# IMX7S_WIRELESS.net
KiCad netlist of a schematic drawn in Altium Designer
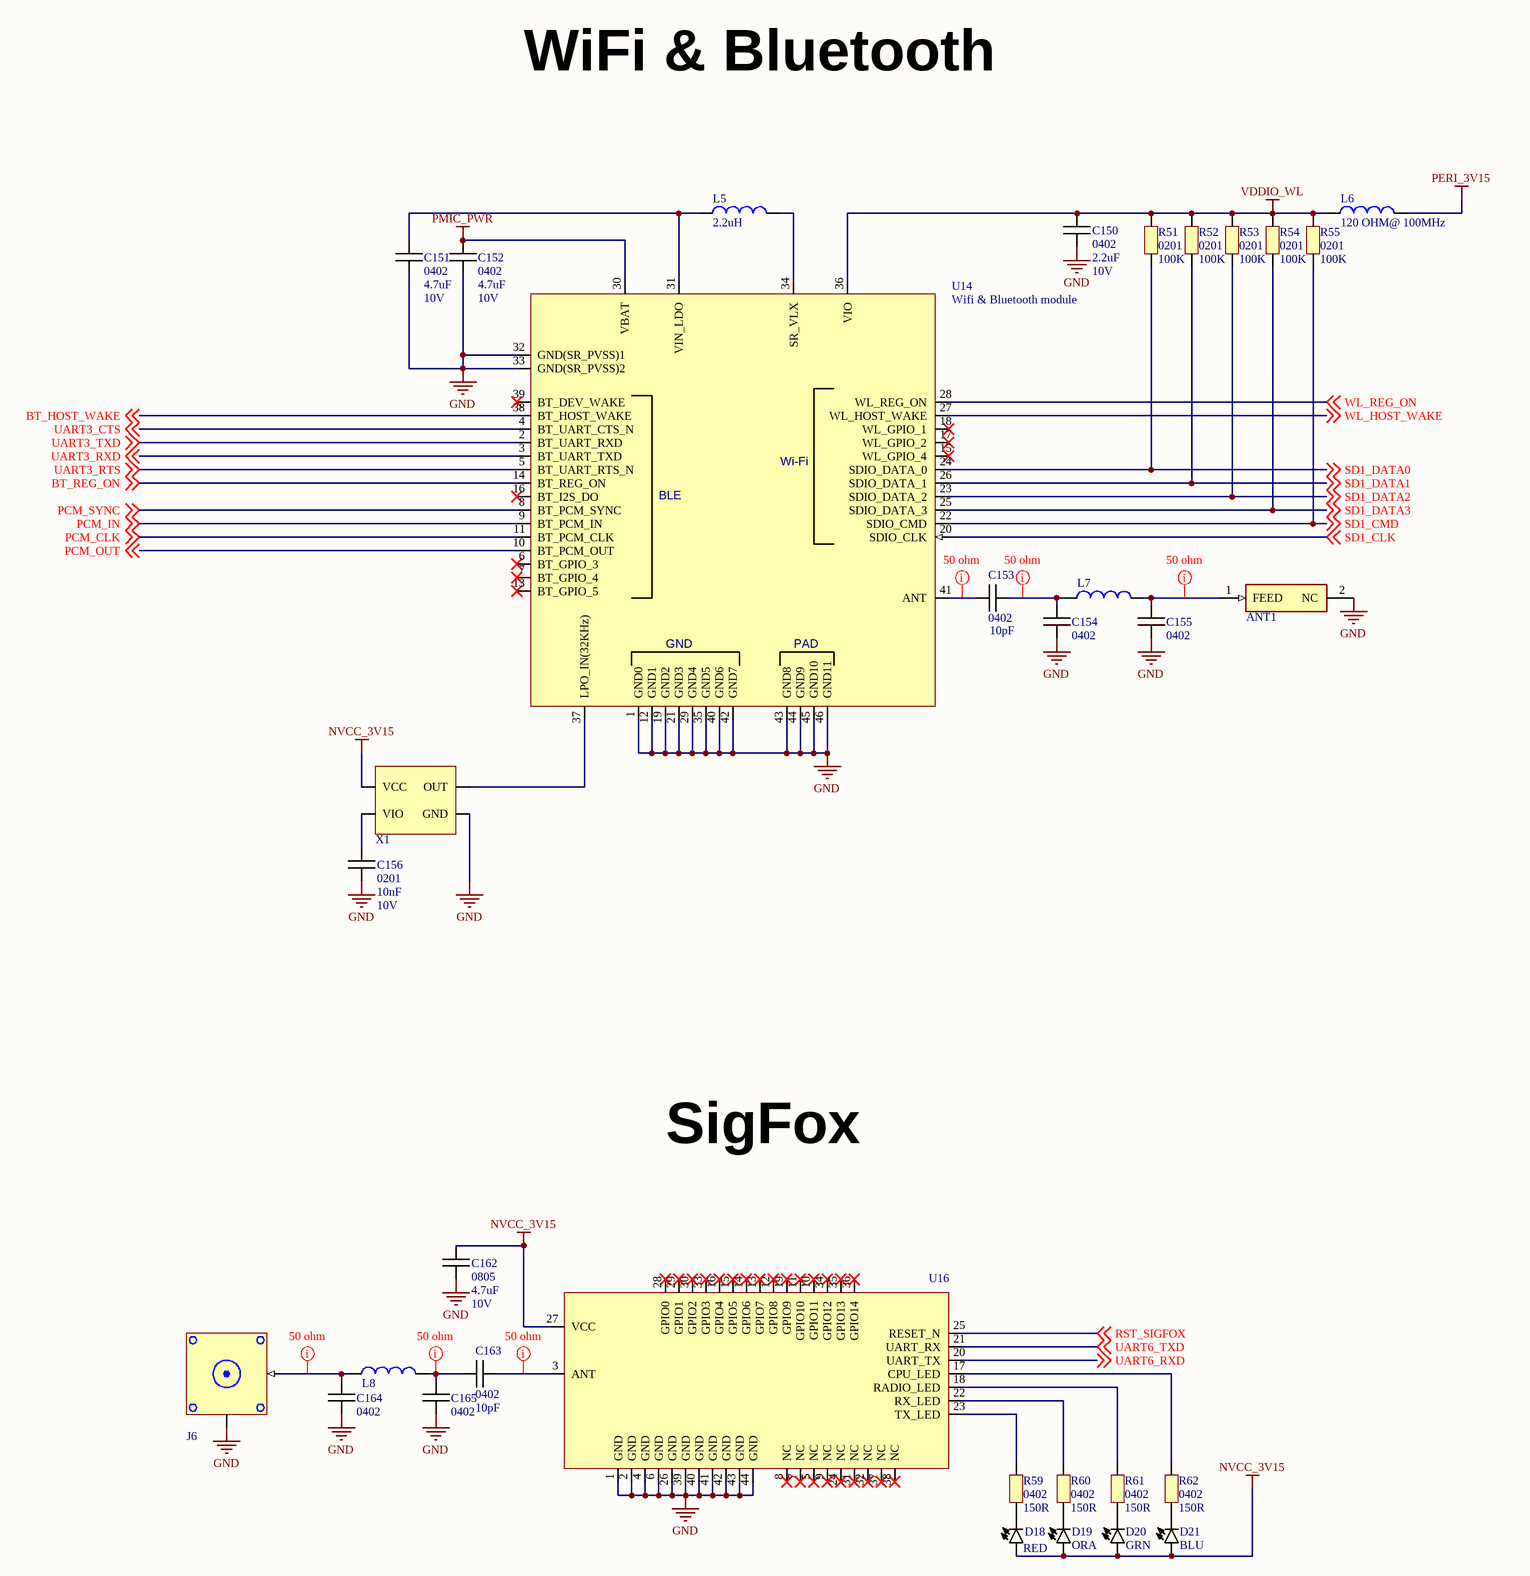
[diagram p0: IMX7S_WIRELESS.SchDoc]

(export (version "E")
  (design (tool "Eeschema 10.0.6"))
  (components
    (comp (ref "ANT1")
      (value "SRCW004")
      (footprint "SRCW004")
      (description "Antenna")
      (fields (field (name "MOUSER PART NUMBER") "237-SRCW004"))
      (libsource (lib "Schlib_IMX7") (part "SRCW004"))
    )
    (comp (ref "C150")
      (value "2.2uF")
      (footprint "C0402")
      (fields
        (field (name "PACKAGE") "0402")
        (field (name "VOLTAGE") "10V")
        (field (name "TOLERANCE") "20%")
        (field (name "Comment") "C0402")
      )
      (libsource (lib "Schlib_IMX7") (part "C0402"))
    )
    (comp (ref "C151")
      (value "4.7uF")
      (footprint "C0402")
      (fields (field (name "PACKAGE") "0402") (field (name "VOLTAGE") "10V") (field (name "Comment") "C0402"))
      (libsource (lib "Schlib_IMX7") (part "C0402"))
    )
    (comp (ref "C152")
      (value "4.7uF")
      (footprint "C0402")
      (fields (field (name "PACKAGE") "0402") (field (name "VOLTAGE") "10V") (field (name "Comment") "C0402"))
      (libsource (lib "Schlib_IMX7") (part "C0402"))
    )
    (comp (ref "C153")
      (value "10pF")
      (footprint "C0402")
      (fields
        (field (name "PACKAGE") "0402")
        (field (name "VOLTAGE") "0V")
        (field (name "TOLERANCE") "1%")
        (field (name "Comment") "C0402")
      )
      (libsource (lib "Schlib_IMX7") (part "C0402"))
    )
    (comp (ref "C154")
      (value "C0402")
      (footprint "C0402")
      (fields (field (name "PACKAGE") "0402") (field (name "VOLTAGE") "0V"))
      (libsource (lib "Schlib_IMX7") (part "C0402"))
    )
    (comp (ref "C155")
      (value "C0402")
      (footprint "C0402")
      (fields (field (name "PACKAGE") "0402") (field (name "VOLTAGE") "0V"))
      (libsource (lib "Schlib_IMX7") (part "C0402"))
    )
    (comp (ref "C156")
      (value "10nF")
      (footprint "C0201")
      (fields (field (name "PACKAGE") "0201") (field (name "VOLTAGE") "10V") (field (name "Comment") "C0201"))
      (libsource (lib "Schlib_IMX7") (part "C0201"))
    )
    (comp (ref "C162")
      (value "4.7uF")
      (footprint "C0805")
      (description "Cap Ceramic 4.7uF 10V X5R 10% SMD 0805 85C Plastic T/R")
      (fields
        (field (name "PACKAGE") "0805")
        (field (name "VOLTAGE") "10V")
        (field (name "TOLERANCE") "10%")
        (field (name "Comment") "C0805")
      )
      (libsource (lib "Schlib_IMX7") (part "C0805"))
    )
    (comp (ref "C163")
      (value "10pF")
      (footprint "C0402")
      (fields
        (field (name "PACKAGE") "0402")
        (field (name "VOLTAGE") "0V")
        (field (name "TOLERANCE") "1%")
        (field (name "Comment") "C0402")
      )
      (libsource (lib "Schlib_IMX7") (part "C0402"))
    )
    (comp (ref "C164")
      (value "C0402")
      (footprint "C0402")
      (fields (field (name "PACKAGE") "0402") (field (name "VOLTAGE") "0V"))
      (libsource (lib "Schlib_IMX7") (part "C0402"))
    )
    (comp (ref "C165")
      (value "C0402")
      (footprint "C0402")
      (fields (field (name "PACKAGE") "0402") (field (name "VOLTAGE") "0V"))
      (libsource (lib "Schlib_IMX7") (part "C0402"))
    )
    (comp (ref "D18") (value "RED") (footprint "D0603") (libsource (lib "Schlib_IMX7") (part "LED")))
    (comp (ref "D19") (value "ORA") (footprint "D0603") (libsource (lib "Schlib_IMX7") (part "LED")))
    (comp (ref "D20") (value "GRN") (footprint "D0603") (libsource (lib "Schlib_IMX7") (part "LED")))
    (comp (ref "D21") (value "BLU") (footprint "D0603") (libsource (lib "Schlib_IMX7") (part "LED")))
    (comp (ref "J6") (value "SMA") (footprint "SMA") (libsource (lib "Schlib_IMX7") (part "SMA")))
    (comp (ref "L5")
      (value "2.2uH")
      (footprint "R0402")
      (fields (field (name "Comment") "Self"))
      (libsource (lib "Schlib_IMX7") (part "Self"))
    )
    (comp (ref "L6")
      (value "120 OHM@ 100MHz")
      (footprint "SELF")
      (fields (field (name "Comment") "Self"))
      (libsource (lib "Schlib_IMX7") (part "Self"))
    )
    (comp (ref "L7") (value "Self") (footprint "R0402") (libsource (lib "Schlib_IMX7") (part "Self")))
    (comp (ref "L8") (value "Self") (footprint "R0402") (libsource (lib "Schlib_IMX7") (part "Self")))
    (comp (ref "R51")
      (value "100K")
      (footprint "R0201")
      (description "MULTICOMP - MCRE000188 - RES, 100K, 1%, 0.05W, 0201, THICK FILM")
      (fields (field (name "PACKAGE") "0201") (field (name "VOLTAGE") "0V") (field (name "TOLERANCE") "1%"))
      (libsource (lib "Schlib_IMX7") (part "R0201"))
    )
    (comp (ref "R52")
      (value "100K")
      (footprint "R0201")
      (description "MULTICOMP - MCRE000188 - RES, 100K, 1%, 0.05W, 0201, THICK FILM")
      (fields (field (name "PACKAGE") "0201") (field (name "VOLTAGE") "0V") (field (name "TOLERANCE") "1%"))
      (libsource (lib "Schlib_IMX7") (part "R0201"))
    )
    (comp (ref "R53")
      (value "100K")
      (footprint "R0201")
      (description "MULTICOMP - MCRE000188 - RES, 100K, 1%, 0.05W, 0201, THICK FILM")
      (fields (field (name "PACKAGE") "0201") (field (name "VOLTAGE") "0V") (field (name "TOLERANCE") "1%"))
      (libsource (lib "Schlib_IMX7") (part "R0201"))
    )
    (comp (ref "R54")
      (value "100K")
      (footprint "R0201")
      (description "MULTICOMP - MCRE000188 - RES, 100K, 1%, 0.05W, 0201, THICK FILM")
      (fields (field (name "PACKAGE") "0201") (field (name "VOLTAGE") "0V") (field (name "TOLERANCE") "1%"))
      (libsource (lib "Schlib_IMX7") (part "R0201"))
    )
    (comp (ref "R55")
      (value "100K")
      (footprint "R0201")
      (description "MULTICOMP - MCRE000188 - RES, 100K, 1%, 0.05W, 0201, THICK FILM")
      (fields (field (name "PACKAGE") "0201") (field (name "VOLTAGE") "0V") (field (name "TOLERANCE") "1%"))
      (libsource (lib "Schlib_IMX7") (part "R0201"))
    )
    (comp (ref "R59")
      (value "150R")
      (footprint "R0402")
      (description "TE Connectivity CRG0402 Series Thick Film Surface Mount Resistor 0402 Case 150 1% 0.063W 100ppm/C")
      (fields (field (name "PACKAGE") "0402") (field (name "VOLTAGE") "0V") (field (name "TOLERANCE") "1%"))
      (libsource (lib "Schlib_IMX7") (part "R0402"))
    )
    (comp (ref "R60")
      (value "150R")
      (footprint "R0402")
      (description "TE Connectivity CRG0402 Series Thick Film Surface Mount Resistor 0402 Case 150 1% 0.063W 100ppm/C")
      (fields (field (name "PACKAGE") "0402") (field (name "VOLTAGE") "0V") (field (name "TOLERANCE") "1%"))
      (libsource (lib "Schlib_IMX7") (part "R0402"))
    )
    (comp (ref "R61")
      (value "150R")
      (footprint "R0402")
      (description "TE Connectivity CRG0402 Series Thick Film Surface Mount Resistor 0402 Case 150 1% 0.063W 100ppm/C")
      (fields (field (name "PACKAGE") "0402") (field (name "VOLTAGE") "0V") (field (name "TOLERANCE") "1%"))
      (libsource (lib "Schlib_IMX7") (part "R0402"))
    )
    (comp (ref "R62")
      (value "150R")
      (footprint "R0402")
      (description "TE Connectivity CRG0402 Series Thick Film Surface Mount Resistor 0402 Case 150 1% 0.063W 100ppm/C")
      (fields (field (name "PACKAGE") "0402") (field (name "VOLTAGE") "0V") (field (name "TOLERANCE") "1%"))
      (libsource (lib "Schlib_IMX7") (part "R0402"))
    )
    (comp (ref "U14")
      (value "Wifi & Bluetooth module")
      (footprint "LBEE5KL1DX")
      (libsource (lib "Schlib_IMX7") (part "LBEE5KL1X-833"))
    )
    (comp (ref "U16")
      (value "AX-SIP-SFEU-1-01-TX30")
      (footprint "AX-SIP-SFEU-1-01-TX30")
      (libsource (lib "Schlib_IMX7") (part "AX-SIP-SFEU-1-01-TX30"))
    )
    (comp (ref "X1")
      (value "X1B0002110001 SG-3030CM 32.768KHZ B")
      (footprint "SPXO")
      (libsource (lib "Schlib_IMX7") (part "Oscillateur"))
    )
  )
  (nets
    (net (code "1") (name "BT_HOST_WAKE") (class "Default")
      (node (ref "U14") (pin "38") (pinfunction "BT_HOST_WAKE_38") (pintype "passive"))
    )
    (net (code "2") (name "BT_REG_ON") (class "Default")
      (node (ref "U14") (pin "14") (pinfunction "BT_REG_ON_14") (pintype "passive"))
    )
    (net (code "3") (name "GND") (class "Default")
      (node (ref "ANT1") (pin "2") (pinfunction "NC_2") (pintype "passive"))
      (node (ref "C150") (pin "1") (pinfunction "1_1") (pintype "passive"))
      (node (ref "C151") (pin "1") (pinfunction "1_1") (pintype "passive"))
      (node (ref "C152") (pin "1") (pinfunction "1_1") (pintype "passive"))
      (node (ref "C154") (pin "1") (pinfunction "1_1") (pintype "passive"))
      (node (ref "C155") (pin "1") (pinfunction "1_1") (pintype "passive"))
      (node (ref "C156") (pin "1") (pinfunction "1_1") (pintype "passive"))
      (node (ref "C162") (pin "1") (pinfunction "1_1") (pintype "passive"))
      (node (ref "C164") (pin "1") (pinfunction "1_1") (pintype "passive"))
      (node (ref "C165") (pin "1") (pinfunction "1_1") (pintype "passive"))
      (node (ref "J6") (pin "2") (pinfunction "GND_2") (pintype "passive"))
      (node (ref "U14") (pin "1") (pinfunction "GND0_1") (pintype "passive"))
      (node (ref "U14") (pin "12") (pinfunction "GND1_12") (pintype "passive"))
      (node (ref "U14") (pin "19") (pinfunction "GND2_19") (pintype "passive"))
      (node (ref "U14") (pin "21") (pinfunction "GND3_21") (pintype "passive"))
      (node (ref "U14") (pin "29") (pinfunction "GND4_29") (pintype "passive"))
      (node (ref "U14") (pin "32") (pinfunction "GND(SR_PVSS)1_32") (pintype "passive"))
      (node (ref "U14") (pin "33") (pinfunction "GND(SR_PVSS)2_33") (pintype "passive"))
      (node (ref "U14") (pin "35") (pinfunction "GND5_35") (pintype "passive"))
      (node (ref "U14") (pin "40") (pinfunction "GND6_40") (pintype "passive"))
      (node (ref "U14") (pin "42") (pinfunction "GND7_42") (pintype "passive"))
      (node (ref "U14") (pin "43") (pinfunction "GND8_43") (pintype "passive"))
      (node (ref "U14") (pin "44") (pinfunction "GND9_44") (pintype "passive"))
      (node (ref "U14") (pin "45") (pinfunction "GND10_45") (pintype "passive"))
      (node (ref "U14") (pin "46") (pinfunction "GND11_46") (pintype "passive"))
      (node (ref "U16") (pin "1") (pinfunction "GND_1") (pintype "passive"))
      (node (ref "U16") (pin "2") (pinfunction "GND_2") (pintype "passive"))
      (node (ref "U16") (pin "26") (pinfunction "GND_26") (pintype "passive"))
      (node (ref "U16") (pin "39") (pinfunction "GND_39") (pintype "passive"))
      (node (ref "U16") (pin "4") (pinfunction "GND_4") (pintype "passive"))
      (node (ref "U16") (pin "40") (pinfunction "GND_40") (pintype "passive"))
      (node (ref "U16") (pin "41") (pinfunction "GND_41") (pintype "passive"))
      (node (ref "U16") (pin "42") (pinfunction "GND_42") (pintype "passive"))
      (node (ref "U16") (pin "43") (pinfunction "GND_43") (pintype "passive"))
      (node (ref "U16") (pin "44") (pinfunction "GND_44") (pintype "passive"))
      (node (ref "U16") (pin "6") (pinfunction "GND_6") (pintype "passive"))
      (node (ref "X1") (pin "2") (pinfunction "GND_2") (pintype "passive"))
    )
    (net (code "4") (name "NVCC_3V15") (class "Default")
      (node (ref "C162") (pin "2") (pinfunction "2_2") (pintype "passive"))
      (node (ref "D18") (pin "1") (pinfunction "A_1") (pintype "passive"))
      (node (ref "D19") (pin "1") (pinfunction "A_1") (pintype "passive"))
      (node (ref "D20") (pin "1") (pinfunction "A_1") (pintype "passive"))
      (node (ref "D21") (pin "1") (pinfunction "A_1") (pintype "passive"))
      (node (ref "U16") (pin "27") (pinfunction "VCC_27") (pintype "passive"))
      (node (ref "X1") (pin "4") (pinfunction "VCC_4") (pintype "passive"))
    )
    (net (code "5") (name "Net-(ANT1-FEED)") (class "Default")
      (node (ref "ANT1") (pin "1") (pinfunction "FEED_1") (pintype "input"))
      (node (ref "C155") (pin "2") (pinfunction "2_2") (pintype "passive"))
      (node (ref "L7") (pin "2") (pintype "passive"))
    )
    (net (code "6") (name "Net-(C153-Pad1)") (class "Default")
      (node (ref "C153") (pin "1") (pinfunction "1_1") (pintype "passive"))
      (node (ref "C154") (pin "2") (pinfunction "2_2") (pintype "passive"))
      (node (ref "L7") (pin "1") (pintype "passive"))
    )
    (net (code "7") (name "Net-(C163-Pad2)") (class "Default")
      (node (ref "C163") (pin "2") (pinfunction "2_2") (pintype "passive"))
      (node (ref "C165") (pin "2") (pinfunction "2_2") (pintype "passive"))
      (node (ref "L8") (pin "2") (pintype "passive"))
    )
    (net (code "8") (name "Net-(C164-Pad2)") (class "Default")
      (node (ref "C164") (pin "2") (pinfunction "2_2") (pintype "passive"))
      (node (ref "J6") (pin "1") (pintype "input"))
      (node (ref "L8") (pin "1") (pintype "passive"))
    )
    (net (code "9") (name "Net-(D18-K)") (class "Default")
      (node (ref "D18") (pin "2") (pinfunction "K_2") (pintype "passive"))
      (node (ref "R59") (pin "1") (pinfunction "1_1") (pintype "passive"))
    )
    (net (code "10") (name "Net-(D19-K)") (class "Default")
      (node (ref "D19") (pin "2") (pinfunction "K_2") (pintype "passive"))
      (node (ref "R60") (pin "1") (pinfunction "1_1") (pintype "passive"))
    )
    (net (code "11") (name "Net-(D20-K)") (class "Default")
      (node (ref "D20") (pin "2") (pinfunction "K_2") (pintype "passive"))
      (node (ref "R61") (pin "1") (pinfunction "1_1") (pintype "passive"))
    )
    (net (code "12") (name "Net-(D21-K)") (class "Default")
      (node (ref "D21") (pin "2") (pinfunction "K_2") (pintype "passive"))
      (node (ref "R62") (pin "1") (pinfunction "1_1") (pintype "passive"))
    )
    (net (code "13") (name "Net-(U14-ANT)") (class "Default")
      (node (ref "C153") (pin "2") (pinfunction "2_2") (pintype "passive"))
      (node (ref "U14") (pin "41") (pinfunction "ANT_41") (pintype "passive"))
    )
    (net (code "14") (name "Net-(U14-LPO_IN(32KHz))") (class "Default")
      (node (ref "U14") (pin "37") (pinfunction "LPO_IN(32KHz)_37") (pintype "passive"))
      (node (ref "X1") (pin "3") (pinfunction "OUT_3") (pintype "passive"))
    )
    (net (code "15") (name "Net-(U14-SR_VLX)") (class "Default")
      (node (ref "L5") (pin "2") (pintype "passive"))
      (node (ref "U14") (pin "34") (pinfunction "SR_VLX_34") (pintype "passive"))
    )
    (net (code "16") (name "Net-(U14-VIN_LDO)") (class "Default")
      (node (ref "C151") (pin "2") (pinfunction "2_2") (pintype "passive"))
      (node (ref "L5") (pin "1") (pintype "passive"))
      (node (ref "U14") (pin "31") (pinfunction "VIN_LDO_31") (pintype "passive"))
    )
    (net (code "17") (name "Net-(U16-ANT)") (class "Default")
      (node (ref "C163") (pin "1") (pinfunction "1_1") (pintype "passive"))
      (node (ref "U16") (pin "3") (pinfunction "ANT_3") (pintype "passive"))
    )
    (net (code "18") (name "Net-(U16-CPU_LED)") (class "Default")
      (node (ref "R62") (pin "2") (pinfunction "2_2") (pintype "passive"))
      (node (ref "U16") (pin "17") (pinfunction "CPU_LED_17") (pintype "passive"))
    )
    (net (code "19") (name "Net-(U16-RADIO_LED)") (class "Default")
      (node (ref "R61") (pin "2") (pinfunction "2_2") (pintype "passive"))
      (node (ref "U16") (pin "18") (pinfunction "RADIO_LED_18") (pintype "passive"))
    )
    (net (code "20") (name "Net-(U16-RX_LED)") (class "Default")
      (node (ref "R60") (pin "2") (pinfunction "2_2") (pintype "passive"))
      (node (ref "U16") (pin "22") (pinfunction "RX_LED_22") (pintype "passive"))
    )
    (net (code "21") (name "Net-(U16-TX_LED)") (class "Default")
      (node (ref "R59") (pin "2") (pinfunction "2_2") (pintype "passive"))
      (node (ref "U16") (pin "23") (pinfunction "TX_LED_23") (pintype "passive"))
    )
    (net (code "22") (name "Net-(X1-VIO)") (class "Default")
      (node (ref "C156") (pin "2") (pinfunction "2_2") (pintype "passive"))
      (node (ref "X1") (pin "1") (pinfunction "VIO_1") (pintype "passive"))
    )
    (net (code "23") (name "PCM_CLK") (class "Default")
      (node (ref "U14") (pin "11") (pinfunction "BT_PCM_CLK_11") (pintype "passive"))
    )
    (net (code "24") (name "PCM_IN") (class "Default")
      (node (ref "U14") (pin "9") (pinfunction "BT_PCM_IN_9") (pintype "passive"))
    )
    (net (code "25") (name "PCM_OUT") (class "Default")
      (node (ref "U14") (pin "10") (pinfunction "BT_PCM_OUT_10") (pintype "passive"))
    )
    (net (code "26") (name "PCM_SYNC") (class "Default")
      (node (ref "U14") (pin "8") (pinfunction "BT_PCM_SYNC_8") (pintype "passive"))
    )
    (net (code "27") (name "PERI_3V15") (class "Default") (node (ref "L6") (pin "2") (pintype "passive")))
    (net (code "28") (name "PMIC_PWR") (class "Default")
      (node (ref "C152") (pin "2") (pinfunction "2_2") (pintype "passive"))
      (node (ref "U14") (pin "30") (pinfunction "VBAT_30") (pintype "passive"))
    )
    (net (code "29") (name "RST_SIGFOX") (class "Default")
      (node (ref "U16") (pin "25") (pinfunction "RESET_N_25") (pintype "passive"))
    )
    (net (code "30") (name "SD1_CLK") (class "Default")
      (node (ref "U14") (pin "20") (pinfunction "SDIO_CLK_20") (pintype "input"))
    )
    (net (code "31") (name "SD1_CMD") (class "Default")
      (node (ref "R55") (pin "1") (pinfunction "1_1") (pintype "passive"))
      (node (ref "U14") (pin "22") (pinfunction "SDIO_CMD_22") (pintype "passive"))
    )
    (net (code "32") (name "SD1_DATA0") (class "Default")
      (node (ref "R51") (pin "1") (pinfunction "1_1") (pintype "passive"))
      (node (ref "U14") (pin "24") (pinfunction "SDIO_DATA_0_24") (pintype "passive"))
    )
    (net (code "33") (name "SD1_DATA1") (class "Default")
      (node (ref "R52") (pin "1") (pinfunction "1_1") (pintype "passive"))
      (node (ref "U14") (pin "26") (pinfunction "SDIO_DATA_1_26") (pintype "passive"))
    )
    (net (code "34") (name "SD1_DATA2") (class "Default")
      (node (ref "R53") (pin "1") (pinfunction "1_1") (pintype "passive"))
      (node (ref "U14") (pin "23") (pinfunction "SDIO_DATA_2_23") (pintype "passive"))
    )
    (net (code "35") (name "SD1_DATA3") (class "Default")
      (node (ref "R54") (pin "1") (pinfunction "1_1") (pintype "passive"))
      (node (ref "U14") (pin "25") (pinfunction "SDIO_DATA_3_25") (pintype "passive"))
    )
    (net (code "36") (name "UART3_CTS") (class "Default")
      (node (ref "U14") (pin "4") (pinfunction "BT_UART_CTS_N_4") (pintype "passive"))
    )
    (net (code "37") (name "UART3_RTS") (class "Default")
      (node (ref "U14") (pin "5") (pinfunction "BT_UART_RTS_N_5") (pintype "passive"))
    )
    (net (code "38") (name "UART3_RXD") (class "Default")
      (node (ref "U14") (pin "3") (pinfunction "BT_UART_TXD_3") (pintype "passive"))
    )
    (net (code "39") (name "UART3_TXD") (class "Default")
      (node (ref "U14") (pin "2") (pinfunction "BT_UART_RXD_2") (pintype "passive"))
    )
    (net (code "40") (name "UART6_RXD") (class "Default")
      (node (ref "U16") (pin "20") (pinfunction "UART_TX_20") (pintype "passive"))
    )
    (net (code "41") (name "UART6_TXD") (class "Default")
      (node (ref "U16") (pin "21") (pinfunction "UART_RX_21") (pintype "passive"))
    )
    (net (code "42") (name "VDDIO_WL") (class "Default")
      (node (ref "C150") (pin "2") (pinfunction "2_2") (pintype "passive"))
      (node (ref "L6") (pin "1") (pintype "passive"))
      (node (ref "R51") (pin "2") (pinfunction "2_2") (pintype "passive"))
      (node (ref "R52") (pin "2") (pinfunction "2_2") (pintype "passive"))
      (node (ref "R53") (pin "2") (pinfunction "2_2") (pintype "passive"))
      (node (ref "R54") (pin "2") (pinfunction "2_2") (pintype "passive"))
      (node (ref "R55") (pin "2") (pinfunction "2_2") (pintype "passive"))
      (node (ref "U14") (pin "36") (pinfunction "VIO_36") (pintype "passive"))
    )
    (net (code "43") (name "WL_HOST_WAKE") (class "Default")
      (node (ref "U14") (pin "27") (pinfunction "WL_HOST_WAKE_27") (pintype "passive"))
    )
    (net (code "44") (name "WL_REG_ON") (class "Default")
      (node (ref "U14") (pin "28") (pinfunction "WL_REG_ON_28") (pintype "passive"))
    )
    (net (code "45") (name "unconnected-(U14-BT_DEV_WAKE-Pad39)") (class "Default")
      (node (ref "U14") (pin "39") (pinfunction "BT_DEV_WAKE_39") (pintype "passive+no_connect"))
    )
    (net (code "46") (name "unconnected-(U14-BT_GPIO_3-Pad6)") (class "Default")
      (node (ref "U14") (pin "6") (pinfunction "BT_GPIO_3_6") (pintype "passive+no_connect"))
    )
    (net (code "47") (name "unconnected-(U14-BT_GPIO_4-Pad7)") (class "Default")
      (node (ref "U14") (pin "7") (pinfunction "BT_GPIO_4_7") (pintype "passive+no_connect"))
    )
    (net (code "48") (name "unconnected-(U14-BT_GPIO_5-Pad13)") (class "Default")
      (node (ref "U14") (pin "13") (pinfunction "BT_GPIO_5_13") (pintype "passive+no_connect"))
    )
    (net (code "49") (name "unconnected-(U14-BT_I2S_DO-Pad16)") (class "Default")
      (node (ref "U14") (pin "16") (pinfunction "BT_I2S_DO_16") (pintype "passive+no_connect"))
    )
    (net (code "50") (name "unconnected-(U14-WL_GPIO_1-Pad18)") (class "Default")
      (node (ref "U14") (pin "18") (pinfunction "WL_GPIO_1_18") (pintype "passive+no_connect"))
    )
    (net (code "51") (name "unconnected-(U14-WL_GPIO_2-Pad17)") (class "Default")
      (node (ref "U14") (pin "17") (pinfunction "WL_GPIO_2_17") (pintype "passive+no_connect"))
    )
    (net (code "52") (name "unconnected-(U14-WL_GPIO_4-Pad15)") (class "Default")
      (node (ref "U14") (pin "15") (pinfunction "WL_GPIO_4_15") (pintype "passive+no_connect"))
    )
    (net (code "53") (name "unconnected-(U16-GPIO0-Pad28)") (class "Default")
      (node (ref "U16") (pin "28") (pinfunction "GPIO0_28") (pintype "passive+no_connect"))
    )
    (net (code "54") (name "unconnected-(U16-GPIO1-Pad29)") (class "Default")
      (node (ref "U16") (pin "29") (pinfunction "GPIO1_29") (pintype "passive+no_connect"))
    )
    (net (code "55") (name "unconnected-(U16-GPIO2-Pad30)") (class "Default")
      (node (ref "U16") (pin "30") (pinfunction "GPIO2_30") (pintype "passive+no_connect"))
    )
    (net (code "56") (name "unconnected-(U16-GPIO3-Pad33)") (class "Default")
      (node (ref "U16") (pin "33") (pinfunction "GPIO3_33") (pintype "passive+no_connect"))
    )
    (net (code "57") (name "unconnected-(U16-GPIO4-Pad16)") (class "Default")
      (node (ref "U16") (pin "16") (pinfunction "GPIO4_16") (pintype "passive+no_connect"))
    )
    (net (code "58") (name "unconnected-(U16-GPIO5-Pad15)") (class "Default")
      (node (ref "U16") (pin "15") (pinfunction "GPIO5_15") (pintype "passive+no_connect"))
    )
    (net (code "59") (name "unconnected-(U16-GPIO6-Pad14)") (class "Default")
      (node (ref "U16") (pin "14") (pinfunction "GPIO6_14") (pintype "passive+no_connect"))
    )
    (net (code "60") (name "unconnected-(U16-GPIO7-Pad13)") (class "Default")
      (node (ref "U16") (pin "13") (pinfunction "GPIO7_13") (pintype "passive+no_connect"))
    )
    (net (code "61") (name "unconnected-(U16-GPIO8-Pad12)") (class "Default")
      (node (ref "U16") (pin "12") (pinfunction "GPIO8_12") (pintype "passive+no_connect"))
    )
    (net (code "62") (name "unconnected-(U16-GPIO9-Pad19)") (class "Default")
      (node (ref "U16") (pin "19") (pinfunction "GPIO9_19") (pintype "passive+no_connect"))
    )
    (net (code "63") (name "unconnected-(U16-GPIO10-Pad11)") (class "Default")
      (node (ref "U16") (pin "11") (pinfunction "GPIO10_11") (pintype "passive+no_connect"))
    )
    (net (code "64") (name "unconnected-(U16-GPIO11-Pad10)") (class "Default")
      (node (ref "U16") (pin "10") (pinfunction "GPIO11_10") (pintype "passive+no_connect"))
    )
    (net (code "65") (name "unconnected-(U16-GPIO12-Pad34)") (class "Default")
      (node (ref "U16") (pin "34") (pinfunction "GPIO12_34") (pintype "passive+no_connect"))
    )
    (net (code "66") (name "unconnected-(U16-GPIO13-Pad35)") (class "Default")
      (node (ref "U16") (pin "35") (pinfunction "GPIO13_35") (pintype "passive+no_connect"))
    )
    (net (code "67") (name "unconnected-(U16-GPIO14-Pad36)") (class "Default")
      (node (ref "U16") (pin "36") (pinfunction "GPIO14_36") (pintype "passive+no_connect"))
    )
    (net (code "68") (name "unconnected-(U16-NC-Pad5)") (class "Default")
      (node (ref "U16") (pin "5") (pinfunction "NC_5") (pintype "passive+no_connect"))
    )
    (net (code "69") (name "unconnected-(U16-NC-Pad7)") (class "Default")
      (node (ref "U16") (pin "7") (pinfunction "NC_7") (pintype "passive+no_connect"))
    )
    (net (code "70") (name "unconnected-(U16-NC-Pad8)") (class "Default")
      (node (ref "U16") (pin "8") (pinfunction "NC_8") (pintype "passive+no_connect"))
    )
    (net (code "71") (name "unconnected-(U16-NC-Pad9)") (class "Default")
      (node (ref "U16") (pin "9") (pinfunction "NC_9") (pintype "passive+no_connect"))
    )
    (net (code "72") (name "unconnected-(U16-NC-Pad24)") (class "Default")
      (node (ref "U16") (pin "24") (pinfunction "NC_24") (pintype "passive+no_connect"))
    )
    (net (code "73") (name "unconnected-(U16-NC-Pad31)") (class "Default")
      (node (ref "U16") (pin "31") (pinfunction "NC_31") (pintype "passive+no_connect"))
    )
    (net (code "74") (name "unconnected-(U16-NC-Pad32)") (class "Default")
      (node (ref "U16") (pin "32") (pinfunction "NC_32") (pintype "passive+no_connect"))
    )
    (net (code "75") (name "unconnected-(U16-NC-Pad37)") (class "Default")
      (node (ref "U16") (pin "37") (pinfunction "NC_37") (pintype "passive+no_connect"))
    )
    (net (code "76") (name "unconnected-(U16-NC-Pad38)") (class "Default")
      (node (ref "U16") (pin "38") (pinfunction "NC_38") (pintype "passive+no_connect"))
    )
  )
)
